# FinalSchematic.net
KiCad netlist of a schematic drawn in Altium Designer
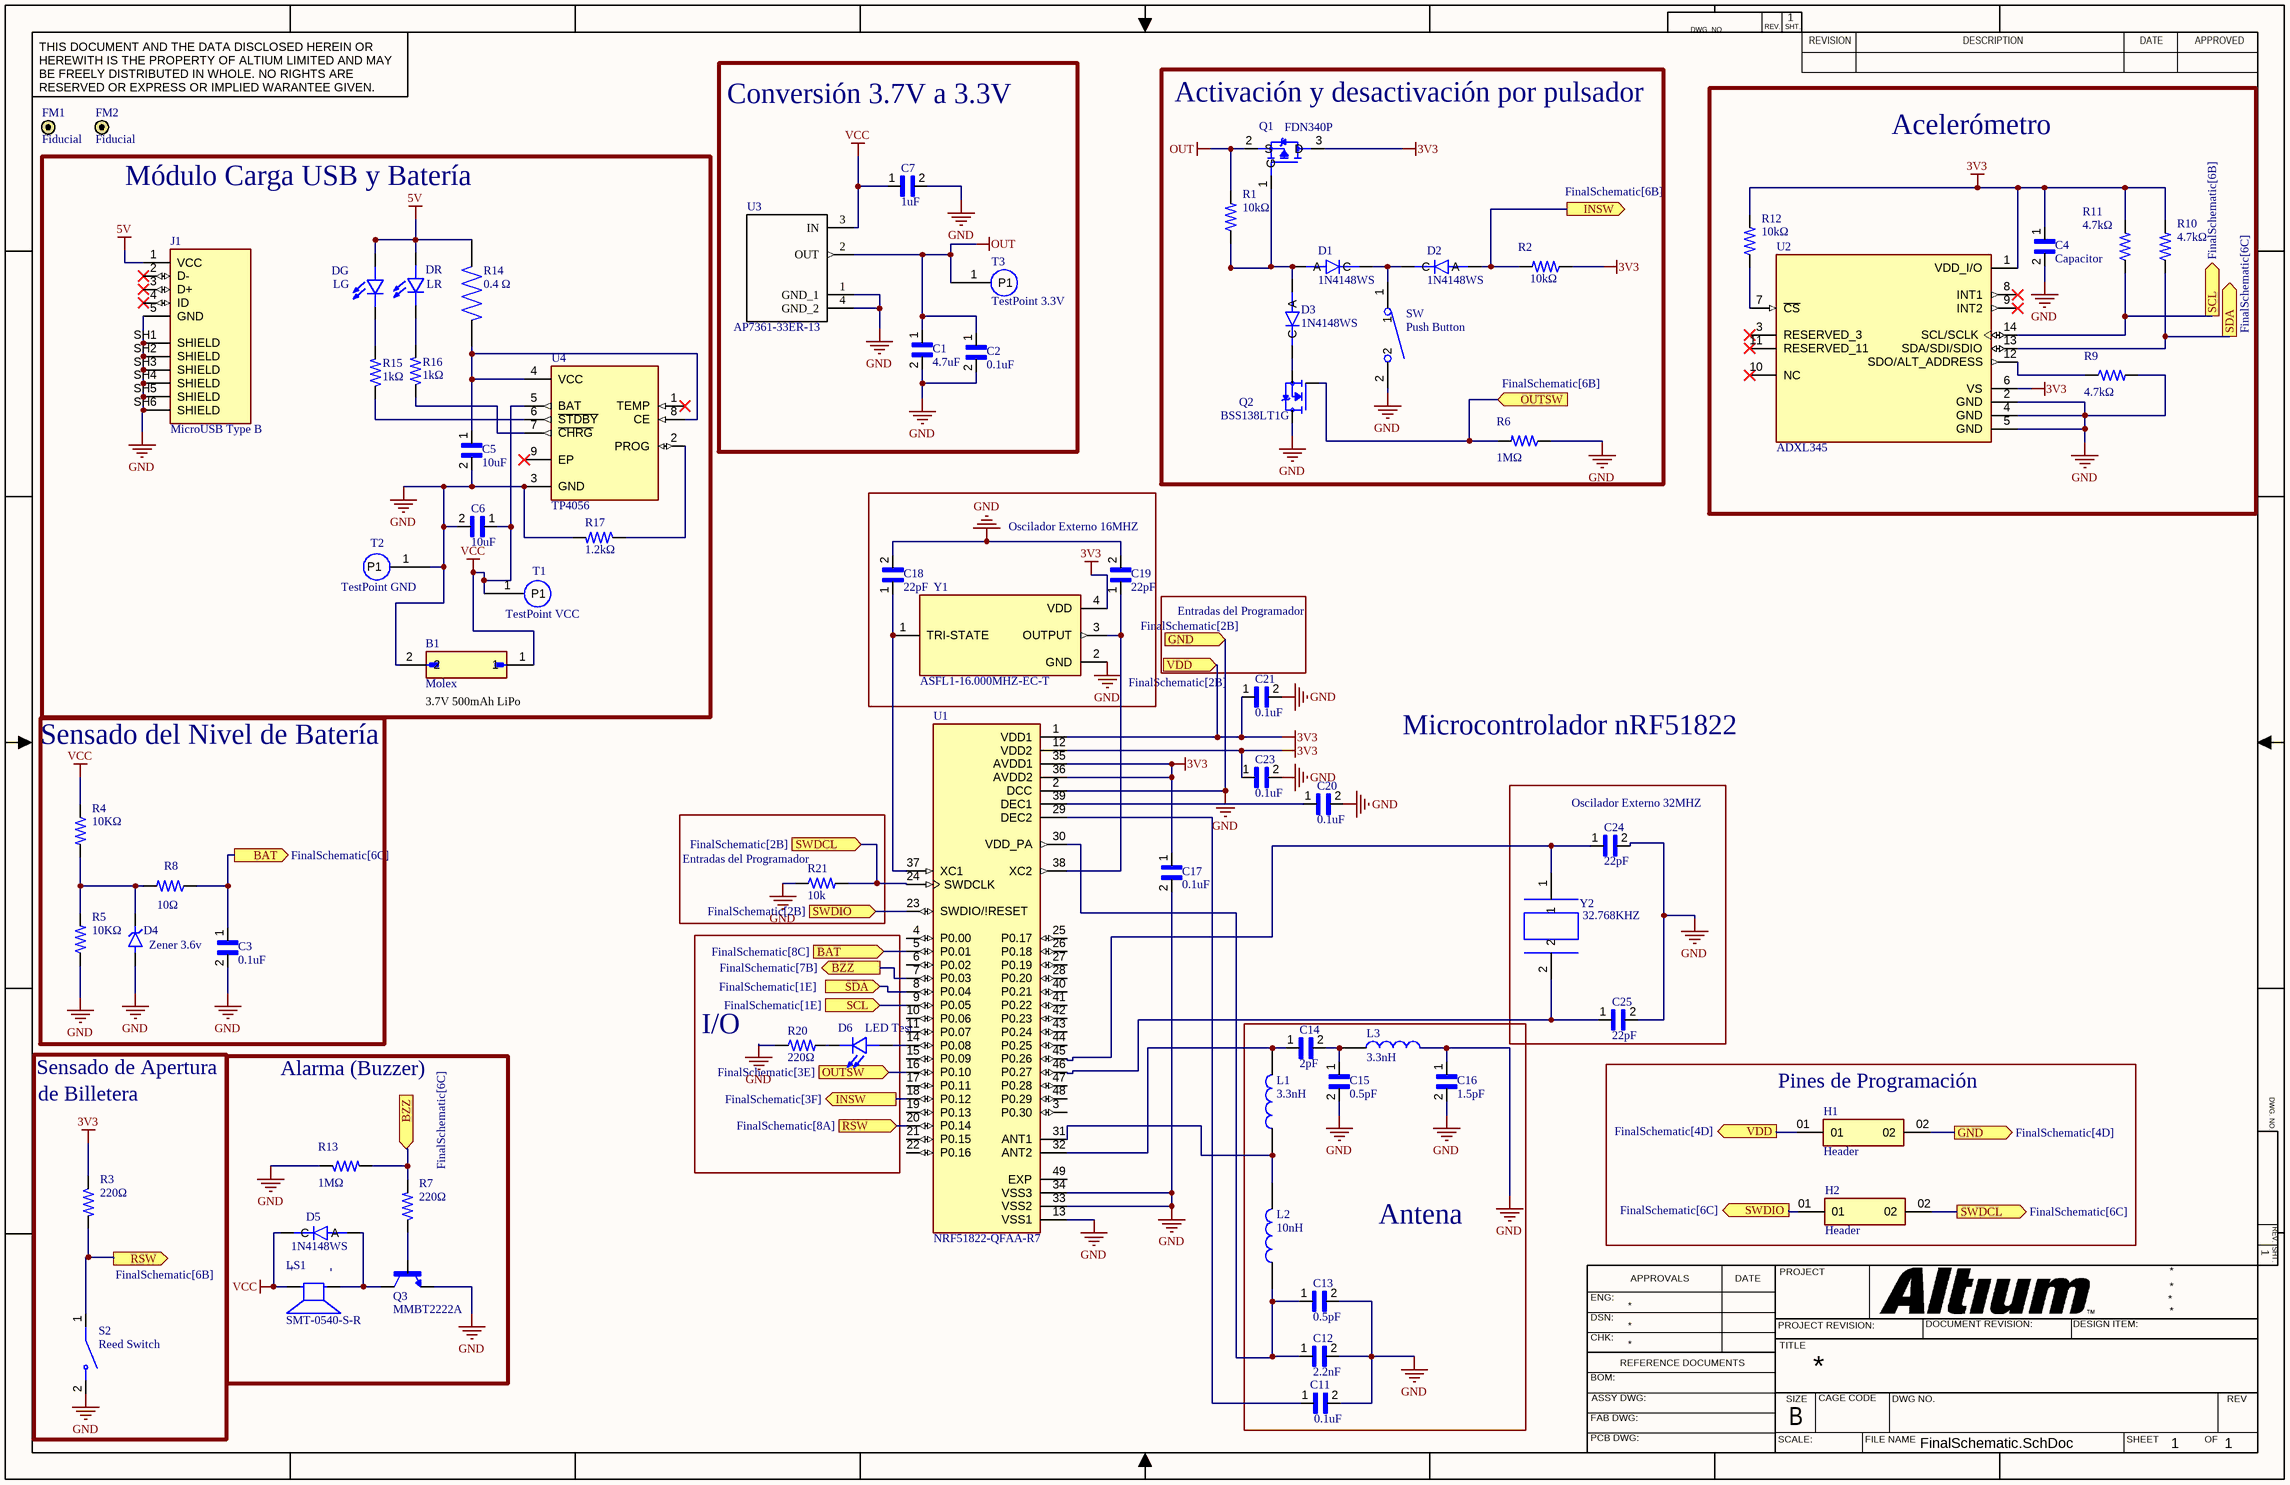
[diagram p0: FinalSchematic.SchDoc]

(export (version "E")
  (design (tool "Eeschema 10.0.6"))
  (components
    (comp (ref "B1")
      (value "Molex")
      (footprint "MOLEX_430450227")
      (fields (field (name "MP") "430450227"))
      (libsource (lib "Schlib1") (part "Molex"))
    )
    (comp (ref "C1")
      (value "4.7uF")
      (footprint "CAPC2012X135N")
      (description "SMD Capacitor X7R(EIA) with Capacitance: 4.7uF Tol. 10%. Rated Voltage: 50Vdc")
      (fields (field (name "MP") "GCM21BR71H104KA37K") (field (name "MF") "Murata"))
      (libsource (lib "Schlib1") (part "GCM21BR71H104KA37K"))
    )
    (comp (ref "C2")
      (value "0.1uF")
      (footprint "CAPC2012X135N")
      (description "SMD Capacitor X7R(EIA) with Capacitance: 0.10uF Tol. 10%. Rated Voltage: 50Vdc")
      (fields (field (name "MP") "GCM21BR71H104KA37K") (field (name "MF") "Murata"))
      (libsource (lib "Schlib1") (part "GCM21BR71H104KA37K"))
    )
    (comp (ref "C3")
      (value "0.1uF")
      (footprint "CAPC1608X94N")
      (description "CAP 0603 0.1uF")
      (fields (field (name "MP") "VJ0603D100MXCAP"))
      (libsource (lib "Schlib1") (part "Capacitor"))
    )
    (comp (ref "C4")
      (value "Capacitor")
      (footprint "CAPC1608X94N")
      (description "CAP 0603 0.1uF")
      (fields (field (name "MP") "VJ0603D100MXCAP"))
      (libsource (lib "Schlib1") (part "Capacitor"))
    )
    (comp (ref "C5")
      (value "10uF")
      (footprint "CAPC2012X135N")
      (description "SMD Capacitor X7R(EIA) with Capacitance: 10uF Tol. 10%. Rated Voltage: 50Vdc")
      (fields (field (name "MP") "GCM21BR71H104KA37K") (field (name "MF") "Murata"))
      (libsource (lib "") (part "GCM21BR71H104KA37K_2"))
    )
    (comp (ref "C6")
      (value "10uF")
      (footprint "CAPC2012X135N")
      (description "SMD Capacitor X7R(EIA) with Capacitance: 10uF Tol. 10%. Rated Voltage: 50Vdc")
      (fields (field (name "MP") "GCM21BR71H104KA37K") (field (name "MF") "Murata"))
      (libsource (lib "Schlib1") (part "GCM21BR71H104KA37K"))
    )
    (comp (ref "C7")
      (value "1uF")
      (footprint "CAPC2012X135N")
      (description "CAP 0603 1uF")
      (fields (field (name "MF") "Murata") (field (name "MP") "GCM21BR71H104KA37K"))
      (libsource (lib "") (part "GCM21BR71H104KA37K_1"))
    )
    (comp (ref "C11")
      (value "0.1uF")
      (footprint "CAPC1608X94N")
      (description "CAP 0603 0.1uF")
      (fields (field (name "MP") "VJ0603D100MXCAP"))
      (libsource (lib "Schlib1") (part "CAP"))
    )
    (comp (ref "C12")
      (value "2.2nF")
      (footprint "CAPC1608X94N")
      (description "CAP 0603 2.2nF")
      (fields (field (name "MP") "VJ0603D100MXCAP"))
      (libsource (lib "Schlib1") (part "CAP"))
    )
    (comp (ref "C13")
      (value "0.5pF")
      (footprint "CAPC1608X94N")
      (description "CAP 0603 0.5pF")
      (fields (field (name "MP") "VJ0603D100MXCAP"))
      (libsource (lib "") (part "Capacitor_1"))
    )
    (comp (ref "C14")
      (value "2pF")
      (footprint "CAPC1608X94N")
      (description "CAP 0603 2pF")
      (fields (field (name "MP") "VJ0603D100MXCAP"))
      (libsource (lib "Schlib1") (part "CAP"))
    )
    (comp (ref "C15")
      (value "0.5pF")
      (footprint "CAPC1608X94N")
      (description "CAP 0603 0.5pF")
      (fields (field (name "MP") "VJ0603D100MXCAP"))
      (libsource (lib "") (part "CAP_2"))
    )
    (comp (ref "C16")
      (value "1.5pF")
      (footprint "CAPC1608X94N")
      (description "CAP 0603 1.5pF")
      (fields (field (name "MP") "VJ0603D100MXCAP"))
      (libsource (lib "") (part "CAP_2"))
    )
    (comp (ref "C17")
      (value "0.1uF")
      (footprint "CAPC1608X94N")
      (description "CAP 0603 0.1uF")
      (fields (field (name "MP") "VJ0603D100MXCAP"))
      (libsource (lib "") (part "CAP_2"))
    )
    (comp (ref "C18")
      (value "22pF")
      (footprint "CAPC1608X94N")
      (description "CAP 0603 22pF")
      (fields (field (name "MP") "VJ0603D100MXCAP"))
      (libsource (lib "") (part "CAP_1"))
    )
    (comp (ref "C19")
      (value "22pF")
      (footprint "CAPC1608X94N")
      (description "CAP 0603 22pF")
      (fields (field (name "MP") "VJ0603D100MXCAP"))
      (libsource (lib "") (part "CAP_1"))
    )
    (comp (ref "C20")
      (value "0.1uF")
      (footprint "CAPC1608X94N")
      (description "CAP 0603 0.1uF")
      (fields (field (name "MP") "VJ0603D100MXCAP"))
      (libsource (lib "Schlib1") (part "CAP"))
    )
    (comp (ref "C21")
      (value "0.1uF")
      (footprint "CAPC1608X94N")
      (description "CAP 0603 0.1uF")
      (fields (field (name "MP") "VJ0603D100MXCAP"))
      (libsource (lib "Schlib1") (part "CAP"))
    )
    (comp (ref "C23")
      (value "0.1uF")
      (footprint "CAPC1608X94N")
      (description "CAP 0603 0.1uF")
      (fields (field (name "MP") "VJ0603D100MXCAP"))
      (libsource (lib "Schlib1") (part "CAP"))
    )
    (comp (ref "C24")
      (value "22pF")
      (footprint "CAPC1608X94N")
      (description "CAP 0603 22pF")
      (fields (field (name "MP") "VJ0603D100MXCAP"))
      (libsource (lib "Schlib1") (part "CAP"))
    )
    (comp (ref "C25")
      (value "22pF")
      (footprint "CAPC1608X94N")
      (description "CAP 0603 22pF")
      (fields (field (name "MP") "VJ0603D100MXCAP"))
      (libsource (lib "Schlib1") (part "CAP"))
    )
    (comp (ref "D1")
      (value "1N4148WS")
      (footprint "1N4148WS")
      (description "1N4148WS, SOD-323F, 100V, 0,15A, 150°C")
      (fields (field (name "MF") "Diotec Semiconductor"))
      (libsource (lib "Schlib1") (part "1N4148WS"))
    )
    (comp (ref "D2")
      (value "1N4148WS")
      (footprint "1N4148WS")
      (description "1N4148WS, SOD-323F, 100V, 0,15A, 150°C")
      (fields (field (name "MF") "Diotec Semiconductor"))
      (libsource (lib "Schlib1") (part "1N4148WS"))
    )
    (comp (ref "D3")
      (value "1N4148WS")
      (footprint "1N4148WS")
      (description "1N4148WS, SOD-323F, 100V, 0,15A, 150°C")
      (fields (field (name "MF") "Diotec Semiconductor"))
      (libsource (lib "Schlib1") (part "1N4148WS"))
    )
    (comp (ref "D4")
      (value "Zener 3.6v")
      (footprint "DIO_BZT52C3V6S")
      (description "Zener Diode 3.6 V 200 mW Â±5% Surface Mount SOD-323F")
      (fields (field (name "MF") "Taiwan Semiconductor") (field (name "MP") "BZT52C3V6S"))
      (libsource (lib "Schlib1") (part "BZT52C3V6S"))
    )
    (comp (ref "D5")
      (value "1N4148WS")
      (footprint "1N4148WS")
      (description "1N4148WS, SOD-323F, 100V, 0,15A, 150°C")
      (fields (field (name "MF") "Diotec Semiconductor"))
      (libsource (lib "Schlib1") (part "1N4148WS"))
    )
    (comp (ref "D6")
      (value "LED Test")
      (footprint "LED_KP-1608SURCK")
      (description "LED; SMD; 0603; red; 50-150mcd; 1.6x0.8mm; 120Â°; 20mA;")
      (fields (field (name "MF") "Kingbright") (field (name "MP") "KP-1608SURCK"))
      (libsource (lib "Schlib1") (part "LED 0603"))
    )
    (comp (ref "DG")
      (value "LG")
      (footprint "LED_KP-1608SURCK")
      (description "LED 0603 SMD White")
      (fields (field (name "MF") "Kingbright") (field (name "MP") "KP-1608SURCK"))
      (libsource (lib "Schlib1") (part "LED 0603"))
    )
    (comp (ref "DR")
      (value "LR")
      (footprint "LED_KP-1608SURCK")
      (description "LED 0603 SMD Red")
      (fields (field (name "MF") "Kingbright") (field (name "MP") "KP-1608SURCK"))
      (libsource (lib "Schlib1") (part "LED 0603"))
    )
    (comp (ref "FM1") (value "Fiducial") (footprint "Fiducial") (libsource (lib "Schlib1") (part "FM?")))
    (comp (ref "FM2") (value "Fiducial") (footprint "Fiducial") (libsource (lib "Schlib1") (part "FM?")))
    (comp (ref "H1")
      (value "Header")
      (footprint "SAMTEC_TMS-101-51-G-D")
      (description "Connector Header Through Hole 2 position")
      (fields (field (name "MF") "Samtec") (field (name "MP") "TMS-101-51-G-D"))
      (libsource (lib "Schlib1") (part "Header"))
    )
    (comp (ref "H2")
      (value "Header")
      (footprint "SAMTEC_TMS-101-51-G-D")
      (description "Connector Header Through Hole 2 position")
      (fields (field (name "MF") "Samtec") (field (name "MP") "TMS-101-51-G-D"))
      (libsource (lib "Schlib1") (part "Header"))
    )
    (comp (ref "J1")
      (value "MicroUSB Type B")
      (footprint "MicroUSB")
      (description "Micro USB, Input Output Connectors, B TYPE RECEPTACLE with flange")
      (fields (field (name "MF") "Amphenol ICC") (field (name "MP") "10118194-0001LF"))
      (libsource (lib "Schlib1") (part "MicroUSB Type B"))
    )
    (comp (ref "L1")
      (value "3.3nH")
      (footprint "INDC1608X95N")
      (description "Inductor with Inductance 3.3nH Package 0603 (1608)")
      (fields (field (name "MP") "LQM18DN100M70L") (field (name "MF") "Murata Electronics"))
      (libsource (lib "Schlib1") (part "L"))
    )
    (comp (ref "L2")
      (value "10nH")
      (footprint "INDC1608X95N")
      (description "Inductor with Inductance 10nH Package 0603 (1608)")
      (fields (field (name "MP") "LQM18DN100M70L") (field (name "MF") "Murata Electronics"))
      (libsource (lib "Schlib1") (part "L"))
    )
    (comp (ref "L3")
      (value "3.3nH")
      (footprint "INDC1608X95N")
      (description "Inductor with Inductance 3.3nH Package 0603 (1608)")
      (fields (field (name "MP") "LQM18DN100M70L") (field (name "MF") "Murata Electronics"))
      (libsource (lib "Schlib1") (part "L"))
    )
    (comp (ref "LS1")
      (value "SMT-0540-S-R")
      (footprint "SMT-0540-S-R")
      (fields (field (name "MF") "{'manufacturer': u'PUI Audio, Inc.'}"))
      (libsource (lib "Schlib1") (part "SMT-0540-S-R"))
    )
    (comp (ref "Q1")
      (value "FDN340P")
      (footprint "SOT95P240X120-3N")
      (description "FDN340P Series 20V 70 mOhm Single P-Ch Logic Level PowerTrench Mosfet SSOT-3")
      (libsource (lib "Schlib1") (part "FDN340P"))
    )
    (comp (ref "Q2")
      (value "BSS138LT1G")
      (footprint "SOT95P237X111-3N")
      (description "N-Channel 50 V 200mA (Ta) 225mW (Ta) Surface Mount SOT-23-3 (TO-236)")
      (fields (field (name "MF") "onsemi"))
      (libsource (lib "Schlib1") (part "BSS138LT1G"))
    )
    (comp (ref "Q3")
      (value "MMBT2222A")
      (footprint "SOT95P240X120-3N")
      (description "BJT, SOT-23, 40V, 600mA, NPN, 0.25W, 150°C")
      (fields (field (name "MF") "Diotec Semiconductor"))
      (libsource (lib "Schlib1") (part "MMBT2222A"))
    )
    (comp (ref "R1")
      (value "10kΩ")
      (footprint "RESC1608X50N")
      (description "10kΩ 0603 Chip Resistor")
      (fields (field (name "MP") "4-2176243-5"))
      (libsource (lib "Schlib1") (part "RES 0603"))
    )
    (comp (ref "R2")
      (value "10kΩ")
      (footprint "RESC1608X50N")
      (description "10kΩ 0603 Chip Resistor")
      (fields (field (name "MP") "4-2176243-5"))
      (libsource (lib "Schlib1") (part "RES 0603"))
    )
    (comp (ref "R3")
      (value "220Ω")
      (footprint "RESC1608X50N")
      (description "220Ω 0603 Chip Resistor")
      (fields (field (name "MP") "4-2176243-5"))
      (libsource (lib "Schlib1") (part "RES 0603"))
    )
    (comp (ref "R4")
      (value "10KΩ")
      (footprint "RESC1608X50N")
      (description "10KΩ 0603 Chip Resistor")
      (fields (field (name "MP") "4-2176243-5"))
      (libsource (lib "Schlib1") (part "RES 0603"))
    )
    (comp (ref "R5")
      (value "10KΩ")
      (footprint "RESC1608X50N")
      (description "10KΩ 0603 Chip Resistor")
      (fields (field (name "MP") "4-2176243-5"))
      (libsource (lib "Schlib1") (part "RES 0603"))
    )
    (comp (ref "R6")
      (value "1MΩ")
      (footprint "RESC1608X50N")
      (description "1MΩ 0603 Chip Resistor")
      (fields (field (name "MP") "4-2176243-5"))
      (libsource (lib "Schlib1") (part "RES 0603"))
    )
    (comp (ref "R7")
      (value "220Ω")
      (footprint "RESC1608X50N")
      (description "220Ω 0603 Chip Resistor")
      (fields (field (name "MP") "4-2176243-5"))
      (libsource (lib "Schlib1") (part "RES 0603"))
    )
    (comp (ref "R8")
      (value "10Ω")
      (footprint "RESC1608X50N")
      (description "10Ω 0603 Chip Resistor")
      (fields (field (name "MP") "4-2176243-5"))
      (libsource (lib "Schlib1") (part "RES 0603"))
    )
    (comp (ref "R9")
      (value "4.7kΩ")
      (footprint "RESC1608X50N")
      (description "4.7kΩ 0603 Chip Resistor")
      (fields (field (name "MP") "4-2176243-5"))
      (libsource (lib "Schlib1") (part "RES 0603"))
    )
    (comp (ref "R10")
      (value "4.7kΩ")
      (footprint "RESC1608X50N")
      (description "4.7kΩ 0603 Chip Resistor")
      (fields (field (name "MP") "4-2176243-5"))
      (libsource (lib "Schlib1") (part "RES 0603"))
    )
    (comp (ref "R11")
      (value "4.7kΩ")
      (footprint "RESC1608X50N")
      (description "4.7kΩ 0603 Chip Resistor")
      (fields (field (name "MP") "4-2176243-5"))
      (libsource (lib "Schlib1") (part "RES 0603"))
    )
    (comp (ref "R12")
      (value "10kΩ")
      (footprint "RESC1608X50N")
      (description "10kΩ 0603 Chip Resistor")
      (fields (field (name "MP") "4-2176243-5"))
      (libsource (lib "Schlib1") (part "RES 0603"))
    )
    (comp (ref "R13")
      (value "1MΩ")
      (footprint "RESC1608X50N")
      (description "1MΩ 0603 Chip Resistor")
      (fields (field (name "MP") "4-2176243-5"))
      (libsource (lib "Schlib1") (part "RES 0603"))
    )
    (comp (ref "R14")
      (value "0.4 Ω")
      (footprint "RESC3116X65N")
      (description "0.4Ω Â±5% 0.25W, 1/4W Chip Resistor 1206 (3216 Metric) Thick Film")
      (fields (field (name "DIGI-KEY_PART_NUMBER") "311-220ERCT-ND") (field (name "MF") "Yageo"))
      (libsource (lib "Schlib1") (part "RC1206JR-07220RL"))
    )
    (comp (ref "R15")
      (value "1kΩ")
      (footprint "RESC1608X50N")
      (description "1kΩ 0603 Chip Resistor")
      (fields (field (name "MP") "4-2176243-5"))
      (libsource (lib "Schlib1") (part "RES 0603"))
    )
    (comp (ref "R16")
      (value "1kΩ")
      (footprint "RESC1608X50N")
      (description "1kΩ 0603 Chip Resistor")
      (fields (field (name "MP") "4-2176243-5"))
      (libsource (lib "Schlib1") (part "RES 0603"))
    )
    (comp (ref "R17")
      (value "1.2kΩ")
      (footprint "RESC1608X50N")
      (description "1.2kΩ 0603 Chip Resistor")
      (fields (field (name "MP") "4-2176243-5"))
      (libsource (lib "Schlib1") (part "RES 0603"))
    )
    (comp (ref "R20")
      (value "220Ω")
      (footprint "RESC1608X50N")
      (description "220Ω 0603 Chip Resistor")
      (fields (field (name "MP") "4-2176243-5"))
      (libsource (lib "Schlib1") (part "RES 0603"))
    )
    (comp (ref "R21")
      (value "10k")
      (footprint "RESC1608X50N")
      (description "10kΩ 0603 Chip Resistor")
      (fields (field (name "MP") "4-2176243-5"))
      (libsource (lib "Schlib1") (part "RES 0603"))
    )
    (comp (ref "S2")
      (value "Reed Switch")
      (footprint "SW_PMC-1001S1015")
      (fields (field (name "MP") "PMC-1001S1015"))
      (libsource (lib "Schlib1") (part "PMC-1001S1015"))
    )
    (comp (ref "SW")
      (value "Push Button")
      (footprint "SW_RS-032G05A3-SMRT")
      (description "Tactile Switch SPST-NO Top Actuated Surface Mount")
      (fields (field (name "MF") "C&K") (field (name "MP") "RS032G05A3SMRT"))
      (libsource (lib "Schlib1") (part "RS-032G05A3-SMRT"))
    )
    (comp (ref "T1") (value "TestPoint VCC") (footprint "Testpoint1") (libsource (lib "Schlib1") (part "T?")))
    (comp (ref "T2") (value "TestPoint GND") (footprint "Testpoint1") (libsource (lib "Schlib1") (part "T?")))
    (comp (ref "T3")
      (value "TestPoint 3.3V")
      (footprint "Testpoint1")
      (libsource (lib "Schlib1") (part "T?"))
    )
    (comp (ref "U1")
      (value "NRF51822-QFAA-R7")
      (footprint "nRf51822")
      (description "IC RF TxRx + MCU Bluetooth, General ISM > 1GHz Bluetooth v4.0 2.4GHz 48-VFQFN Exposed Pad")
      (fields (field (name "MF") "Nordic") (field (name "DIGI-KEY_PART_NUMBER") "1490-1031-1-ND"))
      (libsource (lib "Schlib1") (part "NRF51822-QFAA-R7"))
    )
    (comp (ref "U2")
      (value "ADXL345")
      (footprint "PQFN80P500X300X100-14N")
      (description "Accelerometer X, Y, Z Axis ±2g, 4g, 8g, 16g 0.05Hz ~ 1.6kHz 14-LGA (3x5)")
      (fields (field (name "MF") "Analog Devices, Inc."))
      (libsource (lib "Schlib1") (part "ADXL345"))
    )
    (comp (ref "U3")
      (value "AP7361-33ER-13")
      (footprint "*SOT230P700X180-4N")
      (libsource (lib "Schlib1") (part "AP7361-33ER-13"))
    )
    (comp (ref "U4")
      (value "TP4056")
      (footprint "tp4056")
      (description "Complete single cell Li-Ion battery with a constant current / constant voltage linear charger")
      (fields (field (name "MF") "NanJing Top Power ASIC Corp."))
      (libsource (lib "Schlib1") (part "TP4056"))
    )
    (comp (ref "Y1")
      (value "ASFL1-16.000MHZ-EC-T")
      (footprint "XTAL_ASFL1-16.000MHZ-EC-T")
      (libsource (lib "Schlib1") (part "ASFL1-16.000MHZ-EC-T"))
    )
    (comp (ref "Y2")
      (value "32.768KHZ")
      (footprint "XTAL320X150X75")
      (description "Crystal, 32.768khz, 12.5pf, 3.2 x 1.5mm")
      (fields (field (name "MP") "9HT10-32.768KAZB-T"))
      (libsource (lib "Schlib1") (part "9HT10-32.768KAZB-T"))
    )
  )
  (nets
    (net (code "1") (name "/BAT") (class "Default")
      (node (ref "C3") (pin "1") (pinfunction "1_1") (pintype "passive"))
      (node (ref "R8") (pin "1") (pinfunction "1_1") (pintype "passive"))
      (node (ref "U1") (pin "5") (pinfunction "P0.01_5") (pintype "bidirectional"))
    )
    (net (code "2") (name "/BZZ") (class "Default")
      (node (ref "R13") (pin "2") (pinfunction "2_2") (pintype "passive"))
      (node (ref "R7") (pin "2") (pinfunction "2_2") (pintype "passive"))
      (node (ref "U1") (pin "7") (pinfunction "P0.03_7") (pintype "bidirectional"))
    )
    (net (code "3") (name "/INSW") (class "Default")
      (node (ref "D2") (pin "A") (pinfunction "A_A") (pintype "passive"))
      (node (ref "R2") (pin "2") (pinfunction "2_2") (pintype "passive"))
      (node (ref "U1") (pin "18") (pinfunction "P0.12_18") (pintype "bidirectional"))
    )
    (net (code "4") (name "/OUTSW") (class "Default")
      (node (ref "Q2") (pin "1") (pinfunction "G_1") (pintype "passive"))
      (node (ref "R6") (pin "2") (pinfunction "2_2") (pintype "passive"))
      (node (ref "U1") (pin "16") (pinfunction "P0.10_16") (pintype "bidirectional"))
    )
    (net (code "5") (name "/RSW") (class "Default")
      (node (ref "R3") (pin "2") (pinfunction "2_2") (pintype "passive"))
      (node (ref "S2") (pin "1") (pinfunction "COM_1") (pintype "passive"))
      (node (ref "U1") (pin "20") (pinfunction "P0.14_20") (pintype "bidirectional"))
    )
    (net (code "6") (name "/SCL") (class "Default")
      (node (ref "R11") (pin "1") (pinfunction "1_1") (pintype "passive"))
      (node (ref "U1") (pin "9") (pinfunction "P0.05_9") (pintype "bidirectional"))
      (node (ref "U2") (pin "14") (pinfunction "SCL/SCLK_14") (pintype "bidirectional"))
    )
    (net (code "7") (name "/SDA") (class "Default")
      (node (ref "R10") (pin "1") (pinfunction "1_1") (pintype "passive"))
      (node (ref "U1") (pin "8") (pinfunction "P0.04_8") (pintype "bidirectional"))
      (node (ref "U2") (pin "13") (pinfunction "SDA/SDI/SDIO_13") (pintype "bidirectional"))
    )
    (net (code "8") (name "/SWDCL") (class "Default")
      (node (ref "H2") (pin "02") (pinfunction "02_02") (pintype "passive"))
      (node (ref "R21") (pin "2") (pinfunction "2_2") (pintype "passive"))
      (node (ref "U1") (pin "24") (pinfunction "SWDCLK_24") (pintype "input"))
    )
    (net (code "9") (name "/SWDIO") (class "Default")
      (node (ref "H2") (pin "01") (pinfunction "01_01") (pintype "passive"))
      (node (ref "U1") (pin "23") (pinfunction "SWDIO/!RESET_23") (pintype "bidirectional"))
    )
    (net (code "10") (name "3V3") (class "Default")
      (node (ref "C17") (pin "1") (pinfunction "1_1") (pintype "passive"))
      (node (ref "C21") (pin "1") (pinfunction "1_1") (pintype "passive"))
      (node (ref "C23") (pin "1") (pinfunction "1_1") (pintype "passive"))
      (node (ref "C4") (pin "1") (pinfunction "1_1") (pintype "passive"))
      (node (ref "H1") (pin "01") (pinfunction "01_01") (pintype "passive"))
      (node (ref "Q1") (pin "3") (pinfunction "D_3") (pintype "passive"))
      (node (ref "R10") (pin "2") (pinfunction "2_2") (pintype "passive"))
      (node (ref "R11") (pin "2") (pinfunction "2_2") (pintype "passive"))
      (node (ref "R12") (pin "2") (pinfunction "2_2") (pintype "passive"))
      (node (ref "R2") (pin "1") (pinfunction "1_1") (pintype "passive"))
      (node (ref "R3") (pin "1") (pinfunction "1_1") (pintype "passive"))
      (node (ref "U1") (pin "1") (pinfunction "VDD1_1") (pintype "power_in"))
      (node (ref "U1") (pin "12") (pinfunction "VDD2_12") (pintype "power_in"))
      (node (ref "U1") (pin "35") (pinfunction "AVDD1_35") (pintype "power_in"))
      (node (ref "U1") (pin "36") (pinfunction "AVDD2_36") (pintype "power_in"))
      (node (ref "U2") (pin "1") (pinfunction "VDD_I/O_1") (pintype "power_in"))
      (node (ref "U2") (pin "6") (pinfunction "VS_6") (pintype "power_in"))
      (node (ref "Y1") (pin "4") (pinfunction "VDD_4") (pintype "power_in"))
    )
    (net (code "11") (name "5V") (class "Default")
      (node (ref "DG") (pin "1") (pinfunction "A_1") (pintype "passive"))
      (node (ref "DR") (pin "1") (pinfunction "A_1") (pintype "passive"))
      (node (ref "J1") (pin "1") (pinfunction "VCC_1") (pintype "power_in"))
      (node (ref "R14") (pin "2") (pinfunction "2_2") (pintype "passive"))
    )
    (net (code "12") (name "GND") (class "Default")
      (node (ref "B1") (pin "2") (pinfunction "2_2") (pintype "passive"))
      (node (ref "C1") (pin "2") (pinfunction "2_2") (pintype "passive"))
      (node (ref "C11") (pin "2") (pinfunction "2_2") (pintype "passive"))
      (node (ref "C12") (pin "2") (pinfunction "2_2") (pintype "passive"))
      (node (ref "C13") (pin "2") (pinfunction "2_2") (pintype "passive"))
      (node (ref "C15") (pin "2") (pinfunction "2_2") (pintype "passive"))
      (node (ref "C16") (pin "1") (pinfunction "1_1") (pintype "passive"))
      (node (ref "C16") (pin "2") (pinfunction "2_2") (pintype "passive"))
      (node (ref "C17") (pin "2") (pinfunction "2_2") (pintype "passive"))
      (node (ref "C18") (pin "2") (pinfunction "2_2") (pintype "passive"))
      (node (ref "C19") (pin "2") (pinfunction "2_2") (pintype "passive"))
      (node (ref "C2") (pin "2") (pinfunction "2_2") (pintype "passive"))
      (node (ref "C20") (pin "2") (pinfunction "2_2") (pintype "passive"))
      (node (ref "C21") (pin "2") (pinfunction "2_2") (pintype "passive"))
      (node (ref "C23") (pin "2") (pinfunction "2_2") (pintype "passive"))
      (node (ref "C24") (pin "2") (pinfunction "2_2") (pintype "passive"))
      (node (ref "C25") (pin "2") (pinfunction "2_2") (pintype "passive"))
      (node (ref "C3") (pin "2") (pinfunction "2_2") (pintype "passive"))
      (node (ref "C4") (pin "2") (pinfunction "2_2") (pintype "passive"))
      (node (ref "C5") (pin "2") (pinfunction "2_2") (pintype "passive"))
      (node (ref "C6") (pin "2") (pinfunction "2_2") (pintype "passive"))
      (node (ref "C7") (pin "2") (pinfunction "2_2") (pintype "passive"))
      (node (ref "D4") (pin "A") (pinfunction "A_A") (pintype "passive"))
      (node (ref "H1") (pin "02") (pinfunction "02_02") (pintype "passive"))
      (node (ref "J1") (pin "5") (pinfunction "GND_5") (pintype "power_in"))
      (node (ref "J1") (pin "SH1") (pinfunction "SHIELD_SH1") (pintype "passive"))
      (node (ref "J1") (pin "SH2") (pinfunction "SHIELD_SH2") (pintype "passive"))
      (node (ref "J1") (pin "SH3") (pinfunction "SHIELD_SH3") (pintype "passive"))
      (node (ref "J1") (pin "SH4") (pinfunction "SHIELD_SH4") (pintype "passive"))
      (node (ref "J1") (pin "SH5") (pinfunction "SHIELD_SH5") (pintype "passive"))
      (node (ref "J1") (pin "SH6") (pinfunction "SHIELD_SH6") (pintype "passive"))
      (node (ref "L3") (pin "2") (pinfunction "2_2") (pintype "passive"))
      (node (ref "Q2") (pin "3") (pinfunction "D_3") (pintype "passive"))
      (node (ref "Q3") (pin "2") (pinfunction "E_2") (pintype "passive"))
      (node (ref "R13") (pin "1") (pinfunction "1_1") (pintype "passive"))
      (node (ref "R17") (pin "2") (pinfunction "2_2") (pintype "passive"))
      (node (ref "R20") (pin "1") (pinfunction "1_1") (pintype "passive"))
      (node (ref "R21") (pin "1") (pinfunction "1_1") (pintype "passive"))
      (node (ref "R5") (pin "1") (pinfunction "1_1") (pintype "passive"))
      (node (ref "R6") (pin "1") (pinfunction "1_1") (pintype "passive"))
      (node (ref "R9") (pin "2") (pinfunction "2_2") (pintype "passive"))
      (node (ref "S2") (pin "2") (pinfunction "NO_2") (pintype "passive"))
      (node (ref "SW") (pin "2") (pinfunction "2_2") (pintype "passive"))
      (node (ref "T2") (pin "1") (pinfunction "P1_1") (pintype "passive"))
      (node (ref "U1") (pin "13") (pinfunction "VSS1_13") (pintype "power_in"))
      (node (ref "U1") (pin "2") (pinfunction "DCC_2") (pintype "power_in"))
      (node (ref "U1") (pin "33") (pinfunction "VSS2_33") (pintype "power_in"))
      (node (ref "U1") (pin "34") (pinfunction "VSS3_34") (pintype "power_in"))
      (node (ref "U2") (pin "2") (pinfunction "GND_2") (pintype "power_in"))
      (node (ref "U2") (pin "4") (pinfunction "GND_4") (pintype "power_in"))
      (node (ref "U2") (pin "5") (pinfunction "GND_5") (pintype "power_in"))
      (node (ref "U3") (pin "1") (pinfunction "GND_1_1") (pintype "power_in"))
      (node (ref "U3") (pin "4") (pinfunction "GND_2_4") (pintype "power_in"))
      (node (ref "U4") (pin "3") (pinfunction "GND_3") (pintype "power_in"))
      (node (ref "Y1") (pin "2") (pinfunction "GND_2") (pintype "power_in"))
    )
    (net (code "13") (name "Net-(C14-Pad2)") (class "Default")
      (node (ref "C14") (pin "2") (pinfunction "2_2") (pintype "passive"))
      (node (ref "C15") (pin "1") (pinfunction "1_1") (pintype "passive"))
      (node (ref "L3") (pin "1") (pinfunction "1_1") (pintype "passive"))
    )
    (net (code "14") (name "Net-(D1-PadC)") (class "Default")
      (node (ref "D1") (pin "C") (pinfunction "C_C") (pintype "passive"))
      (node (ref "D2") (pin "C") (pinfunction "C_C") (pintype "passive"))
      (node (ref "SW") (pin "1") (pinfunction "1_1") (pintype "passive"))
    )
    (net (code "15") (name "Net-(D4-K)") (class "Default")
      (node (ref "D4") (pin "C") (pinfunction "K_C") (pintype "passive"))
      (node (ref "R4") (pin "2") (pinfunction "2_2") (pintype "passive"))
      (node (ref "R5") (pin "2") (pinfunction "2_2") (pintype "passive"))
      (node (ref "R8") (pin "2") (pinfunction "2_2") (pintype "passive"))
    )
    (net (code "16") (name "Net-(D6-A)") (class "Default")
      (node (ref "D6") (pin "1") (pinfunction "A_1") (pintype "passive"))
      (node (ref "U1") (pin "14") (pinfunction "P0.08_14") (pintype "bidirectional"))
    )
    (net (code "17") (name "Net-(D6-C)") (class "Default")
      (node (ref "D6") (pin "2") (pinfunction "C_2") (pintype "passive"))
      (node (ref "R20") (pin "2") (pinfunction "2_2") (pintype "passive"))
    )
    (net (code "18") (name "Net-(DG-C)") (class "Default")
      (node (ref "DG") (pin "2") (pinfunction "C_2") (pintype "passive"))
      (node (ref "R15") (pin "2") (pinfunction "2_2") (pintype "passive"))
    )
    (net (code "19") (name "Net-(DR-C)") (class "Default")
      (node (ref "DR") (pin "2") (pinfunction "C_2") (pintype "passive"))
      (node (ref "R16") (pin "2") (pinfunction "2_2") (pintype "passive"))
    )
    (net (code "20") (name "Net-(LS1-NEG)") (class "Default")
      (node (ref "D5") (pin "A") (pinfunction "A_A") (pintype "passive"))
      (node (ref "LS1") (pin "LEAD-") (pinfunction "NEG_LEAD-") (pintype "passive"))
      (node (ref "Q3") (pin "3") (pinfunction "C_3") (pintype "passive"))
    )
    (net (code "21") (name "Net-(Q1-G)") (class "Default")
      (node (ref "D1") (pin "A") (pinfunction "A_A") (pintype "passive"))
      (node (ref "D3") (pin "A") (pinfunction "A_A") (pintype "passive"))
      (node (ref "Q1") (pin "1") (pinfunction "G_1") (pintype "passive"))
      (node (ref "R1") (pin "1") (pinfunction "1_1") (pintype "passive"))
    )
    (net (code "22") (name "Net-(Q2-S)") (class "Default")
      (node (ref "D3") (pin "C") (pinfunction "C_C") (pintype "passive"))
      (node (ref "Q2") (pin "2") (pinfunction "S_2") (pintype "passive"))
    )
    (net (code "23") (name "Net-(Q3-B)") (class "Default")
      (node (ref "Q3") (pin "1") (pinfunction "B_1") (pintype "passive"))
      (node (ref "R7") (pin "1") (pinfunction "1_1") (pintype "passive"))
    )
    (net (code "24") (name "Net-(U1-ANT1)") (class "Default")
      (node (ref "L1") (pin "1") (pinfunction "1_1") (pintype "passive"))
      (node (ref "L2") (pin "2") (pinfunction "2_2") (pintype "passive"))
      (node (ref "U1") (pin "31") (pinfunction "ANT1_31") (pintype "passive"))
    )
    (net (code "25") (name "Net-(U1-ANT2)") (class "Default")
      (node (ref "C14") (pin "1") (pinfunction "1_1") (pintype "passive"))
      (node (ref "L1") (pin "2") (pinfunction "2_2") (pintype "passive"))
      (node (ref "U1") (pin "32") (pinfunction "ANT2_32") (pintype "passive"))
    )
    (net (code "26") (name "Net-(U1-DEC1)") (class "Default")
      (node (ref "C20") (pin "1") (pinfunction "1_1") (pintype "passive"))
      (node (ref "U1") (pin "39") (pinfunction "DEC1_39") (pintype "power_in"))
    )
    (net (code "27") (name "Net-(U1-DEC2)") (class "Default")
      (node (ref "C11") (pin "1") (pinfunction "1_1") (pintype "passive"))
      (node (ref "U1") (pin "29") (pinfunction "DEC2_29") (pintype "power_in"))
    )
    (net (code "28") (name "Net-(U1-P0.26)") (class "Default")
      (node (ref "C24") (pin "1") (pinfunction "1_1") (pintype "passive"))
      (node (ref "U1") (pin "45") (pinfunction "P0.26_45") (pintype "bidirectional"))
      (node (ref "Y2") (pin "1") (pinfunction "1_1") (pintype "passive"))
    )
    (net (code "29") (name "Net-(U1-P0.27)") (class "Default")
      (node (ref "C25") (pin "1") (pinfunction "1_1") (pintype "passive"))
      (node (ref "U1") (pin "46") (pinfunction "P0.27_46") (pintype "bidirectional"))
      (node (ref "Y2") (pin "2") (pinfunction "2_2") (pintype "passive"))
    )
    (net (code "30") (name "Net-(U1-VDD_PA)") (class "Default")
      (node (ref "C12") (pin "1") (pinfunction "1_1") (pintype "passive"))
      (node (ref "C13") (pin "1") (pinfunction "1_1") (pintype "passive"))
      (node (ref "L2") (pin "1") (pinfunction "1_1") (pintype "passive"))
      (node (ref "U1") (pin "30") (pinfunction "VDD_PA_30") (pintype "output"))
    )
    (net (code "31") (name "Net-(U1-XC1)") (class "Default")
      (node (ref "C18") (pin "1") (pinfunction "1_1") (pintype "passive"))
      (node (ref "U1") (pin "37") (pinfunction "XC1_37") (pintype "input"))
      (node (ref "Y1") (pin "1") (pinfunction "TRI-STATE_1") (pintype "passive"))
    )
    (net (code "32") (name "Net-(U1-XC2)") (class "Default")
      (node (ref "C19") (pin "1") (pinfunction "1_1") (pintype "passive"))
      (node (ref "U1") (pin "38") (pinfunction "XC2_38") (pintype "output"))
      (node (ref "Y1") (pin "3") (pinfunction "OUTPUT_3") (pintype "output"))
    )
    (net (code "33") (name "Net-(U2-SDO{slash}ALT_ADDRESS)") (class "Default")
      (node (ref "R9") (pin "1") (pinfunction "1_1") (pintype "passive"))
      (node (ref "U2") (pin "12") (pinfunction "SDO/ALT_ADDRESS_12") (pintype "output"))
    )
    (net (code "34") (name "Net-(U2-~{CS})") (class "Default")
      (node (ref "R12") (pin "1") (pinfunction "1_1") (pintype "passive"))
      (node (ref "U2") (pin "7") (pinfunction "~{CS}_7") (pintype "input"))
    )
    (net (code "35") (name "Net-(U4-CE)") (class "Default")
      (node (ref "C5") (pin "1") (pinfunction "1_1") (pintype "passive"))
      (node (ref "R14") (pin "1") (pinfunction "1_1") (pintype "passive"))
      (node (ref "U4") (pin "4") (pinfunction "VCC_4") (pintype "power_in"))
      (node (ref "U4") (pin "8") (pinfunction "CE_8") (pintype "input"))
    )
    (net (code "36") (name "Net-(U4-PROG)") (class "Default")
      (node (ref "R17") (pin "1") (pinfunction "1_1") (pintype "passive"))
      (node (ref "U4") (pin "2") (pinfunction "PROG_2") (pintype "bidirectional"))
    )
    (net (code "37") (name "Net-(U4-~{CHRG})") (class "Default")
      (node (ref "R16") (pin "1") (pinfunction "1_1") (pintype "passive"))
      (node (ref "U4") (pin "7") (pinfunction "~{CHRG}_7") (pintype "output"))
    )
    (net (code "38") (name "Net-(U4-~{STDBY})") (class "Default")
      (node (ref "R15") (pin "1") (pinfunction "1_1") (pintype "passive"))
      (node (ref "U4") (pin "6") (pinfunction "~{STDBY}_6") (pintype "output"))
    )
    (net (code "39") (name "OUT") (class "Default")
      (node (ref "C1") (pin "1") (pinfunction "1_1") (pintype "passive"))
      (node (ref "C2") (pin "1") (pinfunction "1_1") (pintype "passive"))
      (node (ref "Q1") (pin "2") (pinfunction "S_2") (pintype "passive"))
      (node (ref "R1") (pin "2") (pinfunction "2_2") (pintype "passive"))
      (node (ref "T3") (pin "1") (pinfunction "P1_1") (pintype "passive"))
      (node (ref "U3") (pin "2") (pinfunction "OUT_2") (pintype "output"))
    )
    (net (code "40") (name "VCC") (class "Default")
      (node (ref "B1") (pin "1") (pinfunction "1_1") (pintype "passive"))
      (node (ref "C6") (pin "1") (pinfunction "1_1") (pintype "passive"))
      (node (ref "C7") (pin "1") (pinfunction "1_1") (pintype "passive"))
      (node (ref "D5") (pin "C") (pinfunction "C_C") (pintype "passive"))
      (node (ref "LS1") (pin "LEAD+") (pinfunction "POS_LEAD+") (pintype "passive"))
      (node (ref "R4") (pin "1") (pinfunction "1_1") (pintype "passive"))
      (node (ref "T1") (pin "1") (pinfunction "P1_1") (pintype "passive"))
      (node (ref "U3") (pin "3") (pinfunction "IN_3") (pintype "power_in"))
      (node (ref "U4") (pin "5") (pinfunction "BAT_5") (pintype "output"))
    )
    (net (code "41") (name "unconnected-(J1-D+-Pad3)") (class "Default")
      (node (ref "J1") (pin "3") (pinfunction "D+_3") (pintype "bidirectional+no_connect"))
    )
    (net (code "42") (name "unconnected-(J1-D--Pad2)") (class "Default")
      (node (ref "J1") (pin "2") (pinfunction "D-_2") (pintype "bidirectional+no_connect"))
    )
    (net (code "43") (name "unconnected-(J1-ID-Pad4)") (class "Default")
      (node (ref "J1") (pin "4") (pinfunction "ID_4") (pintype "bidirectional+no_connect"))
    )
    (net (code "44") (name "unconnected-(U1-EXP-Pad49)") (class "Default")
      (node (ref "U1") (pin "49") (pinfunction "EXP_49") (pintype "power_in"))
    )
    (net (code "45") (name "unconnected-(U1-P0.00-Pad4)") (class "Default")
      (node (ref "U1") (pin "4") (pinfunction "P0.00_4") (pintype "bidirectional"))
    )
    (net (code "46") (name "unconnected-(U1-P0.02-Pad6)") (class "Default")
      (node (ref "U1") (pin "6") (pinfunction "P0.02_6") (pintype "bidirectional"))
    )
    (net (code "47") (name "unconnected-(U1-P0.06-Pad10)") (class "Default")
      (node (ref "U1") (pin "10") (pinfunction "P0.06_10") (pintype "bidirectional"))
    )
    (net (code "48") (name "unconnected-(U1-P0.07-Pad11)") (class "Default")
      (node (ref "U1") (pin "11") (pinfunction "P0.07_11") (pintype "bidirectional"))
    )
    (net (code "49") (name "unconnected-(U1-P0.09-Pad15)") (class "Default")
      (node (ref "U1") (pin "15") (pinfunction "P0.09_15") (pintype "bidirectional"))
    )
    (net (code "50") (name "unconnected-(U1-P0.11-Pad17)") (class "Default")
      (node (ref "U1") (pin "17") (pinfunction "P0.11_17") (pintype "bidirectional"))
    )
    (net (code "51") (name "unconnected-(U1-P0.13-Pad19)") (class "Default")
      (node (ref "U1") (pin "19") (pinfunction "P0.13_19") (pintype "bidirectional"))
    )
    (net (code "52") (name "unconnected-(U1-P0.15-Pad21)") (class "Default")
      (node (ref "U1") (pin "21") (pinfunction "P0.15_21") (pintype "bidirectional"))
    )
    (net (code "53") (name "unconnected-(U1-P0.16-Pad22)") (class "Default")
      (node (ref "U1") (pin "22") (pinfunction "P0.16_22") (pintype "bidirectional"))
    )
    (net (code "54") (name "unconnected-(U1-P0.17-Pad25)") (class "Default")
      (node (ref "U1") (pin "25") (pinfunction "P0.17_25") (pintype "bidirectional"))
    )
    (net (code "55") (name "unconnected-(U1-P0.18-Pad26)") (class "Default")
      (node (ref "U1") (pin "26") (pinfunction "P0.18_26") (pintype "bidirectional"))
    )
    (net (code "56") (name "unconnected-(U1-P0.19-Pad27)") (class "Default")
      (node (ref "U1") (pin "27") (pinfunction "P0.19_27") (pintype "bidirectional"))
    )
    (net (code "57") (name "unconnected-(U1-P0.20-Pad28)") (class "Default")
      (node (ref "U1") (pin "28") (pinfunction "P0.20_28") (pintype "bidirectional"))
    )
    (net (code "58") (name "unconnected-(U1-P0.21-Pad40)") (class "Default")
      (node (ref "U1") (pin "40") (pinfunction "P0.21_40") (pintype "bidirectional"))
    )
    (net (code "59") (name "unconnected-(U1-P0.22-Pad41)") (class "Default")
      (node (ref "U1") (pin "41") (pinfunction "P0.22_41") (pintype "bidirectional"))
    )
    (net (code "60") (name "unconnected-(U1-P0.23-Pad42)") (class "Default")
      (node (ref "U1") (pin "42") (pinfunction "P0.23_42") (pintype "bidirectional"))
    )
    (net (code "61") (name "unconnected-(U1-P0.24-Pad43)") (class "Default")
      (node (ref "U1") (pin "43") (pinfunction "P0.24_43") (pintype "bidirectional"))
    )
    (net (code "62") (name "unconnected-(U1-P0.25-Pad44)") (class "Default")
      (node (ref "U1") (pin "44") (pinfunction "P0.25_44") (pintype "bidirectional"))
    )
    (net (code "63") (name "unconnected-(U1-P0.28-Pad47)") (class "Default")
      (node (ref "U1") (pin "47") (pinfunction "P0.28_47") (pintype "bidirectional"))
    )
    (net (code "64") (name "unconnected-(U1-P0.29-Pad48)") (class "Default")
      (node (ref "U1") (pin "48") (pinfunction "P0.29_48") (pintype "bidirectional"))
    )
    (net (code "65") (name "unconnected-(U1-P0.30-Pad3)") (class "Default")
      (node (ref "U1") (pin "3") (pinfunction "P0.30_3") (pintype "bidirectional"))
    )
    (net (code "66") (name "unconnected-(U2-INT1-Pad8)") (class "Default")
      (node (ref "U2") (pin "8") (pinfunction "INT1_8") (pintype "output+no_connect"))
    )
    (net (code "67") (name "unconnected-(U2-INT2-Pad9)") (class "Default")
      (node (ref "U2") (pin "9") (pinfunction "INT2_9") (pintype "output+no_connect"))
    )
    (net (code "68") (name "unconnected-(U2-NC-Pad10)") (class "Default")
      (node (ref "U2") (pin "10") (pinfunction "NC_10") (pintype "passive+no_connect"))
    )
    (net (code "69") (name "unconnected-(U2-RESERVED_3-Pad3)") (class "Default")
      (node (ref "U2") (pin "3") (pinfunction "RESERVED_3_3") (pintype "passive+no_connect"))
    )
    (net (code "70") (name "unconnected-(U2-RESERVED_11-Pad11)") (class "Default")
      (node (ref "U2") (pin "11") (pinfunction "RESERVED_11_11") (pintype "passive+no_connect"))
    )
    (net (code "71") (name "unconnected-(U4-EP-Pad9)") (class "Default")
      (node (ref "U4") (pin "9") (pinfunction "EP_9") (pintype "passive+no_connect"))
    )
    (net (code "72") (name "unconnected-(U4-TEMP-Pad1)") (class "Default")
      (node (ref "U4") (pin "1") (pinfunction "TEMP_1") (pintype "input+no_connect"))
    )
  )
)
